# FLD_Logic_autorouted.net
KiCad netlist of a schematic drawn in EAGLE
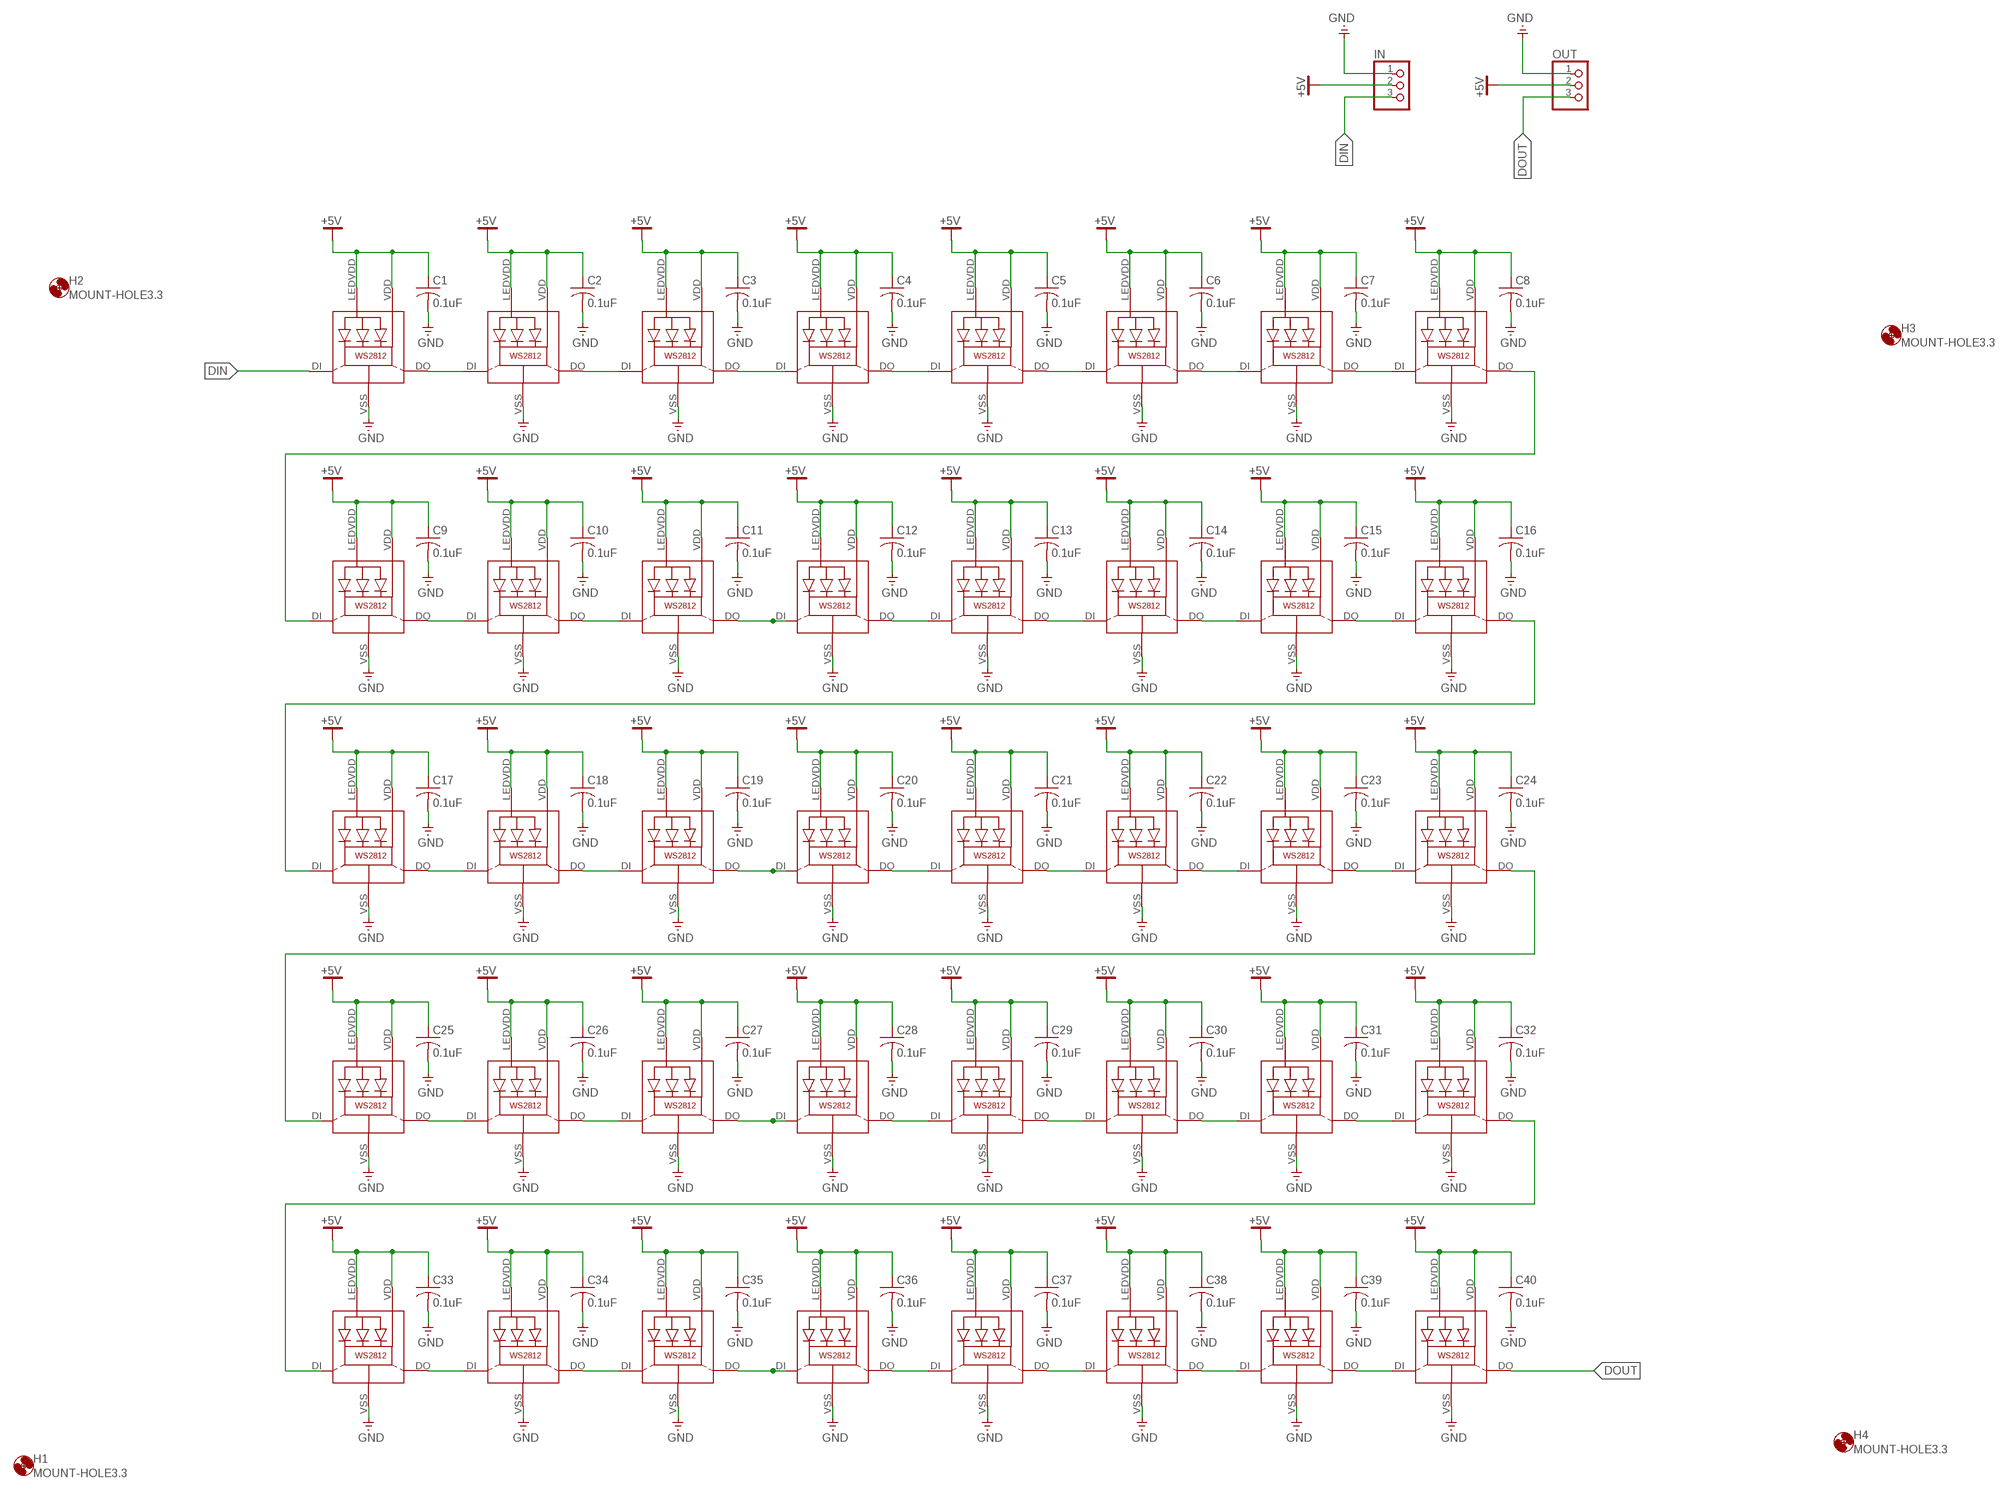
[diagram p0: schematic, sheet 1]

(export (version "E")
  (design (tool "Eeschema 10.0.6"))
  (components
    (comp (ref "C1")
      (value "0.1uF")
      (footprint "eagle-import:C0603")
      (libsource (lib "eagle-import") (part "C-USC0603"))
    )
    (comp (ref "C2")
      (value "0.1uF")
      (footprint "eagle-import:C0603")
      (libsource (lib "eagle-import") (part "C-USC0603"))
    )
    (comp (ref "C3")
      (value "0.1uF")
      (footprint "eagle-import:C0603")
      (libsource (lib "eagle-import") (part "C-USC0603"))
    )
    (comp (ref "C4")
      (value "0.1uF")
      (footprint "eagle-import:C0603")
      (libsource (lib "eagle-import") (part "C-USC0603"))
    )
    (comp (ref "C5")
      (value "0.1uF")
      (footprint "eagle-import:C0603")
      (libsource (lib "eagle-import") (part "C-USC0603"))
    )
    (comp (ref "C6")
      (value "0.1uF")
      (footprint "eagle-import:C0603")
      (libsource (lib "eagle-import") (part "C-USC0603"))
    )
    (comp (ref "C7")
      (value "0.1uF")
      (footprint "eagle-import:C0603")
      (libsource (lib "eagle-import") (part "C-USC0603"))
    )
    (comp (ref "C8")
      (value "0.1uF")
      (footprint "eagle-import:C0603")
      (libsource (lib "eagle-import") (part "C-USC0603"))
    )
    (comp (ref "C9")
      (value "0.1uF")
      (footprint "eagle-import:C0603")
      (libsource (lib "eagle-import") (part "C-USC0603"))
    )
    (comp (ref "C10")
      (value "0.1uF")
      (footprint "eagle-import:C0603")
      (libsource (lib "eagle-import") (part "C-USC0603"))
    )
    (comp (ref "C11")
      (value "0.1uF")
      (footprint "eagle-import:C0603")
      (libsource (lib "eagle-import") (part "C-USC0603"))
    )
    (comp (ref "C12")
      (value "0.1uF")
      (footprint "eagle-import:C0603")
      (libsource (lib "eagle-import") (part "C-USC0603"))
    )
    (comp (ref "C13")
      (value "0.1uF")
      (footprint "eagle-import:C0603")
      (libsource (lib "eagle-import") (part "C-USC0603"))
    )
    (comp (ref "C14")
      (value "0.1uF")
      (footprint "eagle-import:C0603")
      (libsource (lib "eagle-import") (part "C-USC0603"))
    )
    (comp (ref "C15")
      (value "0.1uF")
      (footprint "eagle-import:C0603")
      (libsource (lib "eagle-import") (part "C-USC0603"))
    )
    (comp (ref "C16")
      (value "0.1uF")
      (footprint "eagle-import:C0603")
      (libsource (lib "eagle-import") (part "C-USC0603"))
    )
    (comp (ref "C17")
      (value "0.1uF")
      (footprint "eagle-import:C0603")
      (libsource (lib "eagle-import") (part "C-USC0603"))
    )
    (comp (ref "C18")
      (value "0.1uF")
      (footprint "eagle-import:C0603")
      (libsource (lib "eagle-import") (part "C-USC0603"))
    )
    (comp (ref "C19")
      (value "0.1uF")
      (footprint "eagle-import:C0603")
      (libsource (lib "eagle-import") (part "C-USC0603"))
    )
    (comp (ref "C20")
      (value "0.1uF")
      (footprint "eagle-import:C0603")
      (libsource (lib "eagle-import") (part "C-USC0603"))
    )
    (comp (ref "C21")
      (value "0.1uF")
      (footprint "eagle-import:C0603")
      (libsource (lib "eagle-import") (part "C-USC0603"))
    )
    (comp (ref "C22")
      (value "0.1uF")
      (footprint "eagle-import:C0603")
      (libsource (lib "eagle-import") (part "C-USC0603"))
    )
    (comp (ref "C23")
      (value "0.1uF")
      (footprint "eagle-import:C0603")
      (libsource (lib "eagle-import") (part "C-USC0603"))
    )
    (comp (ref "C24")
      (value "0.1uF")
      (footprint "eagle-import:C0603")
      (libsource (lib "eagle-import") (part "C-USC0603"))
    )
    (comp (ref "C25")
      (value "0.1uF")
      (footprint "eagle-import:C0603")
      (libsource (lib "eagle-import") (part "C-USC0603"))
    )
    (comp (ref "C26")
      (value "0.1uF")
      (footprint "eagle-import:C0603")
      (libsource (lib "eagle-import") (part "C-USC0603"))
    )
    (comp (ref "C27")
      (value "0.1uF")
      (footprint "eagle-import:C0603")
      (libsource (lib "eagle-import") (part "C-USC0603"))
    )
    (comp (ref "C28")
      (value "0.1uF")
      (footprint "eagle-import:C0603")
      (libsource (lib "eagle-import") (part "C-USC0603"))
    )
    (comp (ref "C29")
      (value "0.1uF")
      (footprint "eagle-import:C0603")
      (libsource (lib "eagle-import") (part "C-USC0603"))
    )
    (comp (ref "C30")
      (value "0.1uF")
      (footprint "eagle-import:C0603")
      (libsource (lib "eagle-import") (part "C-USC0603"))
    )
    (comp (ref "C31")
      (value "0.1uF")
      (footprint "eagle-import:C0603")
      (libsource (lib "eagle-import") (part "C-USC0603"))
    )
    (comp (ref "C32")
      (value "0.1uF")
      (footprint "eagle-import:C0603")
      (libsource (lib "eagle-import") (part "C-USC0603"))
    )
    (comp (ref "C33")
      (value "0.1uF")
      (footprint "eagle-import:C0603")
      (libsource (lib "eagle-import") (part "C-USC0603"))
    )
    (comp (ref "C34")
      (value "0.1uF")
      (footprint "eagle-import:C0603")
      (libsource (lib "eagle-import") (part "C-USC0603"))
    )
    (comp (ref "C35")
      (value "0.1uF")
      (footprint "eagle-import:C0603")
      (libsource (lib "eagle-import") (part "C-USC0603"))
    )
    (comp (ref "C36")
      (value "0.1uF")
      (footprint "eagle-import:C0603")
      (libsource (lib "eagle-import") (part "C-USC0603"))
    )
    (comp (ref "C37")
      (value "0.1uF")
      (footprint "eagle-import:C0603")
      (libsource (lib "eagle-import") (part "C-USC0603"))
    )
    (comp (ref "C38")
      (value "0.1uF")
      (footprint "eagle-import:C0603")
      (libsource (lib "eagle-import") (part "C-USC0603"))
    )
    (comp (ref "C39")
      (value "0.1uF")
      (footprint "eagle-import:C0603")
      (libsource (lib "eagle-import") (part "C-USC0603"))
    )
    (comp (ref "C40")
      (value "0.1uF")
      (footprint "eagle-import:C0603")
      (libsource (lib "eagle-import") (part "C-USC0603"))
    )
    (comp (ref "H1")
      (value "MOUNT-HOLE3.3")
      (footprint "eagle-import:3,3")
      (libsource (lib "eagle-import") (part "MOUNT-HOLE3.3"))
    )
    (comp (ref "H2")
      (value "MOUNT-HOLE3.3")
      (footprint "eagle-import:3,3")
      (libsource (lib "eagle-import") (part "MOUNT-HOLE3.3"))
    )
    (comp (ref "H3")
      (value "MOUNT-HOLE3.3")
      (footprint "eagle-import:3,3")
      (libsource (lib "eagle-import") (part "MOUNT-HOLE3.3"))
    )
    (comp (ref "H4")
      (value "MOUNT-HOLE3.3")
      (footprint "eagle-import:3,3")
      (libsource (lib "eagle-import") (part "MOUNT-HOLE3.3"))
    )
    (comp (ref "IN")
      (value "PINHD-1X3")
      (footprint "eagle-import:1X03")
      (libsource (lib "eagle-import") (part "PINHD-1X3"))
    )
    (comp (ref "LED1")
      (value "WS2812")
      (footprint "eagle-import:WS2812")
      (libsource (lib "eagle-import") (part "WS2812"))
    )
    (comp (ref "LED2")
      (value "WS2812")
      (footprint "eagle-import:WS2812")
      (libsource (lib "eagle-import") (part "WS2812"))
    )
    (comp (ref "LED3")
      (value "WS2812")
      (footprint "eagle-import:WS2812")
      (libsource (lib "eagle-import") (part "WS2812"))
    )
    (comp (ref "LED4")
      (value "WS2812")
      (footprint "eagle-import:WS2812")
      (libsource (lib "eagle-import") (part "WS2812"))
    )
    (comp (ref "LED5")
      (value "WS2812")
      (footprint "eagle-import:WS2812")
      (libsource (lib "eagle-import") (part "WS2812"))
    )
    (comp (ref "LED6")
      (value "WS2812")
      (footprint "eagle-import:WS2812")
      (libsource (lib "eagle-import") (part "WS2812"))
    )
    (comp (ref "LED7")
      (value "WS2812")
      (footprint "eagle-import:WS2812")
      (libsource (lib "eagle-import") (part "WS2812"))
    )
    (comp (ref "LED8")
      (value "WS2812")
      (footprint "eagle-import:WS2812")
      (libsource (lib "eagle-import") (part "WS2812"))
    )
    (comp (ref "LED9")
      (value "WS2812")
      (footprint "eagle-import:WS2812")
      (libsource (lib "eagle-import") (part "WS2812"))
    )
    (comp (ref "LED10")
      (value "WS2812")
      (footprint "eagle-import:WS2812")
      (libsource (lib "eagle-import") (part "WS2812"))
    )
    (comp (ref "LED11")
      (value "WS2812")
      (footprint "eagle-import:WS2812")
      (libsource (lib "eagle-import") (part "WS2812"))
    )
    (comp (ref "LED12")
      (value "WS2812")
      (footprint "eagle-import:WS2812")
      (libsource (lib "eagle-import") (part "WS2812"))
    )
    (comp (ref "LED13")
      (value "WS2812")
      (footprint "eagle-import:WS2812")
      (libsource (lib "eagle-import") (part "WS2812"))
    )
    (comp (ref "LED14")
      (value "WS2812")
      (footprint "eagle-import:WS2812")
      (libsource (lib "eagle-import") (part "WS2812"))
    )
    (comp (ref "LED15")
      (value "WS2812")
      (footprint "eagle-import:WS2812")
      (libsource (lib "eagle-import") (part "WS2812"))
    )
    (comp (ref "LED16")
      (value "WS2812")
      (footprint "eagle-import:WS2812")
      (libsource (lib "eagle-import") (part "WS2812"))
    )
    (comp (ref "LED17")
      (value "WS2812")
      (footprint "eagle-import:WS2812")
      (libsource (lib "eagle-import") (part "WS2812"))
    )
    (comp (ref "LED18")
      (value "WS2812")
      (footprint "eagle-import:WS2812")
      (libsource (lib "eagle-import") (part "WS2812"))
    )
    (comp (ref "LED19")
      (value "WS2812")
      (footprint "eagle-import:WS2812")
      (libsource (lib "eagle-import") (part "WS2812"))
    )
    (comp (ref "LED20")
      (value "WS2812")
      (footprint "eagle-import:WS2812")
      (libsource (lib "eagle-import") (part "WS2812"))
    )
    (comp (ref "LED21")
      (value "WS2812")
      (footprint "eagle-import:WS2812")
      (libsource (lib "eagle-import") (part "WS2812"))
    )
    (comp (ref "LED22")
      (value "WS2812")
      (footprint "eagle-import:WS2812")
      (libsource (lib "eagle-import") (part "WS2812"))
    )
    (comp (ref "LED23")
      (value "WS2812")
      (footprint "eagle-import:WS2812")
      (libsource (lib "eagle-import") (part "WS2812"))
    )
    (comp (ref "LED24")
      (value "WS2812")
      (footprint "eagle-import:WS2812")
      (libsource (lib "eagle-import") (part "WS2812"))
    )
    (comp (ref "LED25")
      (value "WS2812")
      (footprint "eagle-import:WS2812")
      (libsource (lib "eagle-import") (part "WS2812"))
    )
    (comp (ref "LED26")
      (value "WS2812")
      (footprint "eagle-import:WS2812")
      (libsource (lib "eagle-import") (part "WS2812"))
    )
    (comp (ref "LED27")
      (value "WS2812")
      (footprint "eagle-import:WS2812")
      (libsource (lib "eagle-import") (part "WS2812"))
    )
    (comp (ref "LED28")
      (value "WS2812")
      (footprint "eagle-import:WS2812")
      (libsource (lib "eagle-import") (part "WS2812"))
    )
    (comp (ref "LED29")
      (value "WS2812")
      (footprint "eagle-import:WS2812")
      (libsource (lib "eagle-import") (part "WS2812"))
    )
    (comp (ref "LED30")
      (value "WS2812")
      (footprint "eagle-import:WS2812")
      (libsource (lib "eagle-import") (part "WS2812"))
    )
    (comp (ref "LED31")
      (value "WS2812")
      (footprint "eagle-import:WS2812")
      (libsource (lib "eagle-import") (part "WS2812"))
    )
    (comp (ref "LED32")
      (value "WS2812")
      (footprint "eagle-import:WS2812")
      (libsource (lib "eagle-import") (part "WS2812"))
    )
    (comp (ref "LED33")
      (value "WS2812")
      (footprint "eagle-import:WS2812")
      (libsource (lib "eagle-import") (part "WS2812"))
    )
    (comp (ref "LED34")
      (value "WS2812")
      (footprint "eagle-import:WS2812")
      (libsource (lib "eagle-import") (part "WS2812"))
    )
    (comp (ref "LED35")
      (value "WS2812")
      (footprint "eagle-import:WS2812")
      (libsource (lib "eagle-import") (part "WS2812"))
    )
    (comp (ref "LED36")
      (value "WS2812")
      (footprint "eagle-import:WS2812")
      (libsource (lib "eagle-import") (part "WS2812"))
    )
    (comp (ref "LED37")
      (value "WS2812")
      (footprint "eagle-import:WS2812")
      (libsource (lib "eagle-import") (part "WS2812"))
    )
    (comp (ref "LED38")
      (value "WS2812")
      (footprint "eagle-import:WS2812")
      (libsource (lib "eagle-import") (part "WS2812"))
    )
    (comp (ref "LED39")
      (value "WS2812")
      (footprint "eagle-import:WS2812")
      (libsource (lib "eagle-import") (part "WS2812"))
    )
    (comp (ref "LED40")
      (value "WS2812")
      (footprint "eagle-import:WS2812")
      (libsource (lib "eagle-import") (part "WS2812"))
    )
    (comp (ref "OUT")
      (value "PINHD-1X3")
      (footprint "eagle-import:1X03")
      (libsource (lib "eagle-import") (part "PINHD-1X3"))
    )
  )
  (nets
    (net (code "1") (name "+5V") (class "Default")
      (node (ref "C1") (pin "1") (pinfunction "1_1") (pintype "passive"))
      (node (ref "C10") (pin "1") (pinfunction "1_1") (pintype "passive"))
      (node (ref "C11") (pin "1") (pinfunction "1_1") (pintype "passive"))
      (node (ref "C12") (pin "1") (pinfunction "1_1") (pintype "passive"))
      (node (ref "C13") (pin "1") (pinfunction "1_1") (pintype "passive"))
      (node (ref "C14") (pin "1") (pinfunction "1_1") (pintype "passive"))
      (node (ref "C15") (pin "1") (pinfunction "1_1") (pintype "passive"))
      (node (ref "C16") (pin "1") (pinfunction "1_1") (pintype "passive"))
      (node (ref "C17") (pin "1") (pinfunction "1_1") (pintype "passive"))
      (node (ref "C18") (pin "1") (pinfunction "1_1") (pintype "passive"))
      (node (ref "C19") (pin "1") (pinfunction "1_1") (pintype "passive"))
      (node (ref "C2") (pin "1") (pinfunction "1_1") (pintype "passive"))
      (node (ref "C20") (pin "1") (pinfunction "1_1") (pintype "passive"))
      (node (ref "C21") (pin "1") (pinfunction "1_1") (pintype "passive"))
      (node (ref "C22") (pin "1") (pinfunction "1_1") (pintype "passive"))
      (node (ref "C23") (pin "1") (pinfunction "1_1") (pintype "passive"))
      (node (ref "C24") (pin "1") (pinfunction "1_1") (pintype "passive"))
      (node (ref "C25") (pin "1") (pinfunction "1_1") (pintype "passive"))
      (node (ref "C26") (pin "1") (pinfunction "1_1") (pintype "passive"))
      (node (ref "C27") (pin "1") (pinfunction "1_1") (pintype "passive"))
      (node (ref "C28") (pin "1") (pinfunction "1_1") (pintype "passive"))
      (node (ref "C29") (pin "1") (pinfunction "1_1") (pintype "passive"))
      (node (ref "C3") (pin "1") (pinfunction "1_1") (pintype "passive"))
      (node (ref "C30") (pin "1") (pinfunction "1_1") (pintype "passive"))
      (node (ref "C31") (pin "1") (pinfunction "1_1") (pintype "passive"))
      (node (ref "C32") (pin "1") (pinfunction "1_1") (pintype "passive"))
      (node (ref "C33") (pin "1") (pinfunction "1_1") (pintype "passive"))
      (node (ref "C34") (pin "1") (pinfunction "1_1") (pintype "passive"))
      (node (ref "C35") (pin "1") (pinfunction "1_1") (pintype "passive"))
      (node (ref "C36") (pin "1") (pinfunction "1_1") (pintype "passive"))
      (node (ref "C37") (pin "1") (pinfunction "1_1") (pintype "passive"))
      (node (ref "C38") (pin "1") (pinfunction "1_1") (pintype "passive"))
      (node (ref "C39") (pin "1") (pinfunction "1_1") (pintype "passive"))
      (node (ref "C4") (pin "1") (pinfunction "1_1") (pintype "passive"))
      (node (ref "C40") (pin "1") (pinfunction "1_1") (pintype "passive"))
      (node (ref "C5") (pin "1") (pinfunction "1_1") (pintype "passive"))
      (node (ref "C6") (pin "1") (pinfunction "1_1") (pintype "passive"))
      (node (ref "C7") (pin "1") (pinfunction "1_1") (pintype "passive"))
      (node (ref "C8") (pin "1") (pinfunction "1_1") (pintype "passive"))
      (node (ref "C9") (pin "1") (pinfunction "1_1") (pintype "passive"))
      (node (ref "IN") (pin "2") (pinfunction "2_2") (pintype "passive"))
      (node (ref "LED1") (pin "LEDVDD") (pinfunction "LEDVDD_LEDVDD") (pintype "power_in"))
      (node (ref "LED1") (pin "VDD") (pinfunction "VDD_VDD") (pintype "power_in"))
      (node (ref "LED10") (pin "LEDVDD") (pinfunction "LEDVDD_LEDVDD") (pintype "power_in"))
      (node (ref "LED10") (pin "VDD") (pinfunction "VDD_VDD") (pintype "power_in"))
      (node (ref "LED11") (pin "LEDVDD") (pinfunction "LEDVDD_LEDVDD") (pintype "power_in"))
      (node (ref "LED11") (pin "VDD") (pinfunction "VDD_VDD") (pintype "power_in"))
      (node (ref "LED12") (pin "LEDVDD") (pinfunction "LEDVDD_LEDVDD") (pintype "power_in"))
      (node (ref "LED12") (pin "VDD") (pinfunction "VDD_VDD") (pintype "power_in"))
      (node (ref "LED13") (pin "LEDVDD") (pinfunction "LEDVDD_LEDVDD") (pintype "power_in"))
      (node (ref "LED13") (pin "VDD") (pinfunction "VDD_VDD") (pintype "power_in"))
      (node (ref "LED14") (pin "LEDVDD") (pinfunction "LEDVDD_LEDVDD") (pintype "power_in"))
      (node (ref "LED14") (pin "VDD") (pinfunction "VDD_VDD") (pintype "power_in"))
      (node (ref "LED15") (pin "LEDVDD") (pinfunction "LEDVDD_LEDVDD") (pintype "power_in"))
      (node (ref "LED15") (pin "VDD") (pinfunction "VDD_VDD") (pintype "power_in"))
      (node (ref "LED16") (pin "LEDVDD") (pinfunction "LEDVDD_LEDVDD") (pintype "power_in"))
      (node (ref "LED16") (pin "VDD") (pinfunction "VDD_VDD") (pintype "power_in"))
      (node (ref "LED17") (pin "LEDVDD") (pinfunction "LEDVDD_LEDVDD") (pintype "power_in"))
      (node (ref "LED17") (pin "VDD") (pinfunction "VDD_VDD") (pintype "power_in"))
      (node (ref "LED18") (pin "LEDVDD") (pinfunction "LEDVDD_LEDVDD") (pintype "power_in"))
      (node (ref "LED18") (pin "VDD") (pinfunction "VDD_VDD") (pintype "power_in"))
      (node (ref "LED19") (pin "LEDVDD") (pinfunction "LEDVDD_LEDVDD") (pintype "power_in"))
      (node (ref "LED19") (pin "VDD") (pinfunction "VDD_VDD") (pintype "power_in"))
      (node (ref "LED2") (pin "LEDVDD") (pinfunction "LEDVDD_LEDVDD") (pintype "power_in"))
      (node (ref "LED2") (pin "VDD") (pinfunction "VDD_VDD") (pintype "power_in"))
      (node (ref "LED20") (pin "LEDVDD") (pinfunction "LEDVDD_LEDVDD") (pintype "power_in"))
      (node (ref "LED20") (pin "VDD") (pinfunction "VDD_VDD") (pintype "power_in"))
      (node (ref "LED21") (pin "LEDVDD") (pinfunction "LEDVDD_LEDVDD") (pintype "power_in"))
      (node (ref "LED21") (pin "VDD") (pinfunction "VDD_VDD") (pintype "power_in"))
      (node (ref "LED22") (pin "LEDVDD") (pinfunction "LEDVDD_LEDVDD") (pintype "power_in"))
      (node (ref "LED22") (pin "VDD") (pinfunction "VDD_VDD") (pintype "power_in"))
      (node (ref "LED23") (pin "LEDVDD") (pinfunction "LEDVDD_LEDVDD") (pintype "power_in"))
      (node (ref "LED23") (pin "VDD") (pinfunction "VDD_VDD") (pintype "power_in"))
      (node (ref "LED24") (pin "LEDVDD") (pinfunction "LEDVDD_LEDVDD") (pintype "power_in"))
      (node (ref "LED24") (pin "VDD") (pinfunction "VDD_VDD") (pintype "power_in"))
      (node (ref "LED25") (pin "LEDVDD") (pinfunction "LEDVDD_LEDVDD") (pintype "power_in"))
      (node (ref "LED25") (pin "VDD") (pinfunction "VDD_VDD") (pintype "power_in"))
      (node (ref "LED26") (pin "LEDVDD") (pinfunction "LEDVDD_LEDVDD") (pintype "power_in"))
      (node (ref "LED26") (pin "VDD") (pinfunction "VDD_VDD") (pintype "power_in"))
      (node (ref "LED27") (pin "LEDVDD") (pinfunction "LEDVDD_LEDVDD") (pintype "power_in"))
      (node (ref "LED27") (pin "VDD") (pinfunction "VDD_VDD") (pintype "power_in"))
      (node (ref "LED28") (pin "LEDVDD") (pinfunction "LEDVDD_LEDVDD") (pintype "power_in"))
      (node (ref "LED28") (pin "VDD") (pinfunction "VDD_VDD") (pintype "power_in"))
      (node (ref "LED29") (pin "LEDVDD") (pinfunction "LEDVDD_LEDVDD") (pintype "power_in"))
      (node (ref "LED29") (pin "VDD") (pinfunction "VDD_VDD") (pintype "power_in"))
      (node (ref "LED3") (pin "LEDVDD") (pinfunction "LEDVDD_LEDVDD") (pintype "power_in"))
      (node (ref "LED3") (pin "VDD") (pinfunction "VDD_VDD") (pintype "power_in"))
      (node (ref "LED30") (pin "LEDVDD") (pinfunction "LEDVDD_LEDVDD") (pintype "power_in"))
      (node (ref "LED30") (pin "VDD") (pinfunction "VDD_VDD") (pintype "power_in"))
      (node (ref "LED31") (pin "LEDVDD") (pinfunction "LEDVDD_LEDVDD") (pintype "power_in"))
      (node (ref "LED31") (pin "VDD") (pinfunction "VDD_VDD") (pintype "power_in"))
      (node (ref "LED32") (pin "LEDVDD") (pinfunction "LEDVDD_LEDVDD") (pintype "power_in"))
      (node (ref "LED32") (pin "VDD") (pinfunction "VDD_VDD") (pintype "power_in"))
      (node (ref "LED33") (pin "LEDVDD") (pinfunction "LEDVDD_LEDVDD") (pintype "power_in"))
      (node (ref "LED33") (pin "VDD") (pinfunction "VDD_VDD") (pintype "power_in"))
      (node (ref "LED34") (pin "LEDVDD") (pinfunction "LEDVDD_LEDVDD") (pintype "power_in"))
      (node (ref "LED34") (pin "VDD") (pinfunction "VDD_VDD") (pintype "power_in"))
      (node (ref "LED35") (pin "LEDVDD") (pinfunction "LEDVDD_LEDVDD") (pintype "power_in"))
      (node (ref "LED35") (pin "VDD") (pinfunction "VDD_VDD") (pintype "power_in"))
      (node (ref "LED36") (pin "LEDVDD") (pinfunction "LEDVDD_LEDVDD") (pintype "power_in"))
      (node (ref "LED36") (pin "VDD") (pinfunction "VDD_VDD") (pintype "power_in"))
      (node (ref "LED37") (pin "LEDVDD") (pinfunction "LEDVDD_LEDVDD") (pintype "power_in"))
      (node (ref "LED37") (pin "VDD") (pinfunction "VDD_VDD") (pintype "power_in"))
      (node (ref "LED38") (pin "LEDVDD") (pinfunction "LEDVDD_LEDVDD") (pintype "power_in"))
      (node (ref "LED38") (pin "VDD") (pinfunction "VDD_VDD") (pintype "power_in"))
      (node (ref "LED39") (pin "LEDVDD") (pinfunction "LEDVDD_LEDVDD") (pintype "power_in"))
      (node (ref "LED39") (pin "VDD") (pinfunction "VDD_VDD") (pintype "power_in"))
      (node (ref "LED4") (pin "LEDVDD") (pinfunction "LEDVDD_LEDVDD") (pintype "power_in"))
      (node (ref "LED4") (pin "VDD") (pinfunction "VDD_VDD") (pintype "power_in"))
      (node (ref "LED40") (pin "LEDVDD") (pinfunction "LEDVDD_LEDVDD") (pintype "power_in"))
      (node (ref "LED40") (pin "VDD") (pinfunction "VDD_VDD") (pintype "power_in"))
      (node (ref "LED5") (pin "LEDVDD") (pinfunction "LEDVDD_LEDVDD") (pintype "power_in"))
      (node (ref "LED5") (pin "VDD") (pinfunction "VDD_VDD") (pintype "power_in"))
      (node (ref "LED6") (pin "LEDVDD") (pinfunction "LEDVDD_LEDVDD") (pintype "power_in"))
      (node (ref "LED6") (pin "VDD") (pinfunction "VDD_VDD") (pintype "power_in"))
      (node (ref "LED7") (pin "LEDVDD") (pinfunction "LEDVDD_LEDVDD") (pintype "power_in"))
      (node (ref "LED7") (pin "VDD") (pinfunction "VDD_VDD") (pintype "power_in"))
      (node (ref "LED8") (pin "LEDVDD") (pinfunction "LEDVDD_LEDVDD") (pintype "power_in"))
      (node (ref "LED8") (pin "VDD") (pinfunction "VDD_VDD") (pintype "power_in"))
      (node (ref "LED9") (pin "LEDVDD") (pinfunction "LEDVDD_LEDVDD") (pintype "power_in"))
      (node (ref "LED9") (pin "VDD") (pinfunction "VDD_VDD") (pintype "power_in"))
      (node (ref "OUT") (pin "2") (pinfunction "2_2") (pintype "passive"))
    )
    (net (code "2") (name "DIN") (class "Default")
      (node (ref "IN") (pin "3") (pinfunction "3_3") (pintype "passive"))
      (node (ref "LED1") (pin "DI") (pinfunction "DI_DI") (pintype "input"))
    )
    (net (code "3") (name "DOUT") (class "Default")
      (node (ref "LED40") (pin "DO") (pinfunction "DO_DO") (pintype "output"))
      (node (ref "OUT") (pin "3") (pinfunction "3_3") (pintype "passive"))
    )
    (net (code "4") (name "GND") (class "Default")
      (node (ref "C1") (pin "2") (pinfunction "2_2") (pintype "passive"))
      (node (ref "C10") (pin "2") (pinfunction "2_2") (pintype "passive"))
      (node (ref "C11") (pin "2") (pinfunction "2_2") (pintype "passive"))
      (node (ref "C12") (pin "2") (pinfunction "2_2") (pintype "passive"))
      (node (ref "C13") (pin "2") (pinfunction "2_2") (pintype "passive"))
      (node (ref "C14") (pin "2") (pinfunction "2_2") (pintype "passive"))
      (node (ref "C15") (pin "2") (pinfunction "2_2") (pintype "passive"))
      (node (ref "C16") (pin "2") (pinfunction "2_2") (pintype "passive"))
      (node (ref "C17") (pin "2") (pinfunction "2_2") (pintype "passive"))
      (node (ref "C18") (pin "2") (pinfunction "2_2") (pintype "passive"))
      (node (ref "C19") (pin "2") (pinfunction "2_2") (pintype "passive"))
      (node (ref "C2") (pin "2") (pinfunction "2_2") (pintype "passive"))
      (node (ref "C20") (pin "2") (pinfunction "2_2") (pintype "passive"))
      (node (ref "C21") (pin "2") (pinfunction "2_2") (pintype "passive"))
      (node (ref "C22") (pin "2") (pinfunction "2_2") (pintype "passive"))
      (node (ref "C23") (pin "2") (pinfunction "2_2") (pintype "passive"))
      (node (ref "C24") (pin "2") (pinfunction "2_2") (pintype "passive"))
      (node (ref "C25") (pin "2") (pinfunction "2_2") (pintype "passive"))
      (node (ref "C26") (pin "2") (pinfunction "2_2") (pintype "passive"))
      (node (ref "C27") (pin "2") (pinfunction "2_2") (pintype "passive"))
      (node (ref "C28") (pin "2") (pinfunction "2_2") (pintype "passive"))
      (node (ref "C29") (pin "2") (pinfunction "2_2") (pintype "passive"))
      (node (ref "C3") (pin "2") (pinfunction "2_2") (pintype "passive"))
      (node (ref "C30") (pin "2") (pinfunction "2_2") (pintype "passive"))
      (node (ref "C31") (pin "2") (pinfunction "2_2") (pintype "passive"))
      (node (ref "C32") (pin "2") (pinfunction "2_2") (pintype "passive"))
      (node (ref "C33") (pin "2") (pinfunction "2_2") (pintype "passive"))
      (node (ref "C34") (pin "2") (pinfunction "2_2") (pintype "passive"))
      (node (ref "C35") (pin "2") (pinfunction "2_2") (pintype "passive"))
      (node (ref "C36") (pin "2") (pinfunction "2_2") (pintype "passive"))
      (node (ref "C37") (pin "2") (pinfunction "2_2") (pintype "passive"))
      (node (ref "C38") (pin "2") (pinfunction "2_2") (pintype "passive"))
      (node (ref "C39") (pin "2") (pinfunction "2_2") (pintype "passive"))
      (node (ref "C4") (pin "2") (pinfunction "2_2") (pintype "passive"))
      (node (ref "C40") (pin "2") (pinfunction "2_2") (pintype "passive"))
      (node (ref "C5") (pin "2") (pinfunction "2_2") (pintype "passive"))
      (node (ref "C6") (pin "2") (pinfunction "2_2") (pintype "passive"))
      (node (ref "C7") (pin "2") (pinfunction "2_2") (pintype "passive"))
      (node (ref "C8") (pin "2") (pinfunction "2_2") (pintype "passive"))
      (node (ref "C9") (pin "2") (pinfunction "2_2") (pintype "passive"))
      (node (ref "IN") (pin "1") (pinfunction "1_1") (pintype "passive"))
      (node (ref "LED1") (pin "VSS") (pinfunction "GND_VSS") (pintype "power_in"))
      (node (ref "LED10") (pin "VSS") (pinfunction "GND_VSS") (pintype "power_in"))
      (node (ref "LED11") (pin "VSS") (pinfunction "GND_VSS") (pintype "power_in"))
      (node (ref "LED12") (pin "VSS") (pinfunction "GND_VSS") (pintype "power_in"))
      (node (ref "LED13") (pin "VSS") (pinfunction "GND_VSS") (pintype "power_in"))
      (node (ref "LED14") (pin "VSS") (pinfunction "GND_VSS") (pintype "power_in"))
      (node (ref "LED15") (pin "VSS") (pinfunction "GND_VSS") (pintype "power_in"))
      (node (ref "LED16") (pin "VSS") (pinfunction "GND_VSS") (pintype "power_in"))
      (node (ref "LED17") (pin "VSS") (pinfunction "GND_VSS") (pintype "power_in"))
      (node (ref "LED18") (pin "VSS") (pinfunction "GND_VSS") (pintype "power_in"))
      (node (ref "LED19") (pin "VSS") (pinfunction "GND_VSS") (pintype "power_in"))
      (node (ref "LED2") (pin "VSS") (pinfunction "GND_VSS") (pintype "power_in"))
      (node (ref "LED20") (pin "VSS") (pinfunction "GND_VSS") (pintype "power_in"))
      (node (ref "LED21") (pin "VSS") (pinfunction "GND_VSS") (pintype "power_in"))
      (node (ref "LED22") (pin "VSS") (pinfunction "GND_VSS") (pintype "power_in"))
      (node (ref "LED23") (pin "VSS") (pinfunction "GND_VSS") (pintype "power_in"))
      (node (ref "LED24") (pin "VSS") (pinfunction "GND_VSS") (pintype "power_in"))
      (node (ref "LED25") (pin "VSS") (pinfunction "GND_VSS") (pintype "power_in"))
      (node (ref "LED26") (pin "VSS") (pinfunction "GND_VSS") (pintype "power_in"))
      (node (ref "LED27") (pin "VSS") (pinfunction "GND_VSS") (pintype "power_in"))
      (node (ref "LED28") (pin "VSS") (pinfunction "GND_VSS") (pintype "power_in"))
      (node (ref "LED29") (pin "VSS") (pinfunction "GND_VSS") (pintype "power_in"))
      (node (ref "LED3") (pin "VSS") (pinfunction "GND_VSS") (pintype "power_in"))
      (node (ref "LED30") (pin "VSS") (pinfunction "GND_VSS") (pintype "power_in"))
      (node (ref "LED31") (pin "VSS") (pinfunction "GND_VSS") (pintype "power_in"))
      (node (ref "LED32") (pin "VSS") (pinfunction "GND_VSS") (pintype "power_in"))
      (node (ref "LED33") (pin "VSS") (pinfunction "GND_VSS") (pintype "power_in"))
      (node (ref "LED34") (pin "VSS") (pinfunction "GND_VSS") (pintype "power_in"))
      (node (ref "LED35") (pin "VSS") (pinfunction "GND_VSS") (pintype "power_in"))
      (node (ref "LED36") (pin "VSS") (pinfunction "GND_VSS") (pintype "power_in"))
      (node (ref "LED37") (pin "VSS") (pinfunction "GND_VSS") (pintype "power_in"))
      (node (ref "LED38") (pin "VSS") (pinfunction "GND_VSS") (pintype "power_in"))
      (node (ref "LED39") (pin "VSS") (pinfunction "GND_VSS") (pintype "power_in"))
      (node (ref "LED4") (pin "VSS") (pinfunction "GND_VSS") (pintype "power_in"))
      (node (ref "LED40") (pin "VSS") (pinfunction "GND_VSS") (pintype "power_in"))
      (node (ref "LED5") (pin "VSS") (pinfunction "GND_VSS") (pintype "power_in"))
      (node (ref "LED6") (pin "VSS") (pinfunction "GND_VSS") (pintype "power_in"))
      (node (ref "LED7") (pin "VSS") (pinfunction "GND_VSS") (pintype "power_in"))
      (node (ref "LED8") (pin "VSS") (pinfunction "GND_VSS") (pintype "power_in"))
      (node (ref "LED9") (pin "VSS") (pinfunction "GND_VSS") (pintype "power_in"))
      (node (ref "OUT") (pin "1") (pinfunction "1_1") (pintype "passive"))
    )
    (net (code "5") (name "Net-(LED1-PadDO)") (class "Default")
      (node (ref "LED1") (pin "DO") (pinfunction "DO_DO") (pintype "output"))
      (node (ref "LED2") (pin "DI") (pinfunction "DI_DI") (pintype "input"))
    )
    (net (code "6") (name "Net-(LED2-PadDO)") (class "Default")
      (node (ref "LED2") (pin "DO") (pinfunction "DO_DO") (pintype "output"))
      (node (ref "LED3") (pin "DI") (pinfunction "DI_DI") (pintype "input"))
    )
    (net (code "7") (name "Net-(LED4-PadDO)") (class "Default")
      (node (ref "LED4") (pin "DO") (pinfunction "DO_DO") (pintype "output"))
      (node (ref "LED5") (pin "DI") (pinfunction "DI_DI") (pintype "input"))
    )
    (net (code "8") (name "Net-(LED5-PadDO)") (class "Default")
      (node (ref "LED5") (pin "DO") (pinfunction "DO_DO") (pintype "output"))
      (node (ref "LED6") (pin "DI") (pinfunction "DI_DI") (pintype "input"))
    )
    (net (code "9") (name "Net-(LED6-PadDO)") (class "Default")
      (node (ref "LED6") (pin "DO") (pinfunction "DO_DO") (pintype "output"))
      (node (ref "LED7") (pin "DI") (pinfunction "DI_DI") (pintype "input"))
    )
    (net (code "10") (name "Net-(LED7-PadDO)") (class "Default")
      (node (ref "LED7") (pin "DO") (pinfunction "DO_DO") (pintype "output"))
      (node (ref "LED8") (pin "DI") (pinfunction "DI_DI") (pintype "input"))
    )
    (net (code "11") (name "Net-(LED8-PadDO)") (class "Default")
      (node (ref "LED8") (pin "DO") (pinfunction "DO_DO") (pintype "output"))
      (node (ref "LED9") (pin "DI") (pinfunction "DI_DI") (pintype "input"))
    )
    (net (code "12") (name "Net-(LED10-PadDI)") (class "Default")
      (node (ref "LED10") (pin "DI") (pinfunction "DI_DI") (pintype "input"))
      (node (ref "LED9") (pin "DO") (pinfunction "DO_DO") (pintype "output"))
    )
    (net (code "13") (name "Net-(LED10-PadDO)") (class "Default")
      (node (ref "LED10") (pin "DO") (pinfunction "DO_DO") (pintype "output"))
      (node (ref "LED11") (pin "DI") (pinfunction "DI_DI") (pintype "input"))
    )
    (net (code "14") (name "Net-(LED11-PadDO)") (class "Default")
      (node (ref "LED11") (pin "DO") (pinfunction "DO_DO") (pintype "output"))
      (node (ref "LED12") (pin "DI") (pinfunction "DI_DI") (pintype "input"))
    )
    (net (code "15") (name "Net-(LED12-PadDO)") (class "Default")
      (node (ref "LED12") (pin "DO") (pinfunction "DO_DO") (pintype "output"))
      (node (ref "LED13") (pin "DI") (pinfunction "DI_DI") (pintype "input"))
    )
    (net (code "16") (name "Net-(LED13-PadDO)") (class "Default")
      (node (ref "LED13") (pin "DO") (pinfunction "DO_DO") (pintype "output"))
      (node (ref "LED14") (pin "DI") (pinfunction "DI_DI") (pintype "input"))
    )
    (net (code "17") (name "Net-(LED14-PadDO)") (class "Default")
      (node (ref "LED14") (pin "DO") (pinfunction "DO_DO") (pintype "output"))
      (node (ref "LED15") (pin "DI") (pinfunction "DI_DI") (pintype "input"))
    )
    (net (code "18") (name "Net-(LED15-PadDO)") (class "Default")
      (node (ref "LED15") (pin "DO") (pinfunction "DO_DO") (pintype "output"))
      (node (ref "LED16") (pin "DI") (pinfunction "DI_DI") (pintype "input"))
    )
    (net (code "19") (name "Net-(LED16-PadDO)") (class "Default")
      (node (ref "LED16") (pin "DO") (pinfunction "DO_DO") (pintype "output"))
      (node (ref "LED17") (pin "DI") (pinfunction "DI_DI") (pintype "input"))
    )
    (net (code "20") (name "Net-(LED17-PadDO)") (class "Default")
      (node (ref "LED17") (pin "DO") (pinfunction "DO_DO") (pintype "output"))
      (node (ref "LED18") (pin "DI") (pinfunction "DI_DI") (pintype "input"))
    )
    (net (code "21") (name "Net-(LED18-PadDO)") (class "Default")
      (node (ref "LED18") (pin "DO") (pinfunction "DO_DO") (pintype "output"))
      (node (ref "LED19") (pin "DI") (pinfunction "DI_DI") (pintype "input"))
    )
    (net (code "22") (name "Net-(LED19-PadDO)") (class "Default")
      (node (ref "LED19") (pin "DO") (pinfunction "DO_DO") (pintype "output"))
      (node (ref "LED20") (pin "DI") (pinfunction "DI_DI") (pintype "input"))
    )
    (net (code "23") (name "Net-(LED20-PadDO)") (class "Default")
      (node (ref "LED20") (pin "DO") (pinfunction "DO_DO") (pintype "output"))
      (node (ref "LED21") (pin "DI") (pinfunction "DI_DI") (pintype "input"))
    )
    (net (code "24") (name "Net-(LED21-PadDO)") (class "Default")
      (node (ref "LED21") (pin "DO") (pinfunction "DO_DO") (pintype "output"))
      (node (ref "LED22") (pin "DI") (pinfunction "DI_DI") (pintype "input"))
    )
    (net (code "25") (name "Net-(LED22-PadDO)") (class "Default")
      (node (ref "LED22") (pin "DO") (pinfunction "DO_DO") (pintype "output"))
      (node (ref "LED23") (pin "DI") (pinfunction "DI_DI") (pintype "input"))
    )
    (net (code "26") (name "Net-(LED23-PadDO)") (class "Default")
      (node (ref "LED23") (pin "DO") (pinfunction "DO_DO") (pintype "output"))
      (node (ref "LED24") (pin "DI") (pinfunction "DI_DI") (pintype "input"))
    )
    (net (code "27") (name "Net-(LED25-PadDO)") (class "Default")
      (node (ref "LED25") (pin "DO") (pinfunction "DO_DO") (pintype "output"))
      (node (ref "LED26") (pin "DI") (pinfunction "DI_DI") (pintype "input"))
    )
    (net (code "28") (name "Net-(LED26-PadDO)") (class "Default")
      (node (ref "LED26") (pin "DO") (pinfunction "DO_DO") (pintype "output"))
      (node (ref "LED27") (pin "DI") (pinfunction "DI_DI") (pintype "input"))
    )
    (net (code "29") (name "Net-(LED27-PadDO)") (class "Default")
      (node (ref "LED27") (pin "DO") (pinfunction "DO_DO") (pintype "output"))
      (node (ref "LED28") (pin "DI") (pinfunction "DI_DI") (pintype "input"))
    )
    (net (code "30") (name "Net-(LED28-PadDO)") (class "Default")
      (node (ref "LED28") (pin "DO") (pinfunction "DO_DO") (pintype "output"))
      (node (ref "LED29") (pin "DI") (pinfunction "DI_DI") (pintype "input"))
    )
    (net (code "31") (name "Net-(LED29-PadDO)") (class "Default")
      (node (ref "LED29") (pin "DO") (pinfunction "DO_DO") (pintype "output"))
      (node (ref "LED30") (pin "DI") (pinfunction "DI_DI") (pintype "input"))
    )
    (net (code "32") (name "Net-(LED30-PadDO)") (class "Default")
      (node (ref "LED30") (pin "DO") (pinfunction "DO_DO") (pintype "output"))
      (node (ref "LED31") (pin "DI") (pinfunction "DI_DI") (pintype "input"))
    )
    (net (code "33") (name "Net-(LED31-PadDO)") (class "Default")
      (node (ref "LED31") (pin "DO") (pinfunction "DO_DO") (pintype "output"))
      (node (ref "LED32") (pin "DI") (pinfunction "DI_DI") (pintype "input"))
    )
    (net (code "34") (name "Net-(LED33-PadDO)") (class "Default")
      (node (ref "LED33") (pin "DO") (pinfunction "DO_DO") (pintype "output"))
      (node (ref "LED34") (pin "DI") (pinfunction "DI_DI") (pintype "input"))
    )
    (net (code "35") (name "Net-(LED34-PadDO)") (class "Default")
      (node (ref "LED34") (pin "DO") (pinfunction "DO_DO") (pintype "output"))
      (node (ref "LED35") (pin "DI") (pinfunction "DI_DI") (pintype "input"))
    )
    (net (code "36") (name "Net-(LED35-PadDO)") (class "Default")
      (node (ref "LED35") (pin "DO") (pinfunction "DO_DO") (pintype "output"))
      (node (ref "LED36") (pin "DI") (pinfunction "DI_DI") (pintype "input"))
    )
    (net (code "37") (name "Net-(LED36-PadDO)") (class "Default")
      (node (ref "LED36") (pin "DO") (pinfunction "DO_DO") (pintype "output"))
      (node (ref "LED37") (pin "DI") (pinfunction "DI_DI") (pintype "input"))
    )
    (net (code "38") (name "Net-(LED37-PadDO)") (class "Default")
      (node (ref "LED37") (pin "DO") (pinfunction "DO_DO") (pintype "output"))
      (node (ref "LED38") (pin "DI") (pinfunction "DI_DI") (pintype "input"))
    )
    (net (code "39") (name "Net-(LED38-PadDO)") (class "Default")
      (node (ref "LED38") (pin "DO") (pinfunction "DO_DO") (pintype "output"))
      (node (ref "LED39") (pin "DI") (pinfunction "DI_DI") (pintype "input"))
    )
    (net (code "40") (name "Net-(LED39-PadDO)") (class "Default")
      (node (ref "LED39") (pin "DO") (pinfunction "DO_DO") (pintype "output"))
      (node (ref "LED40") (pin "DI") (pinfunction "DI_DI") (pintype "input"))
    )
    (net (code "41") (name "unconnected-(LED3-PadDO)") (class "Default")
      (node (ref "LED3") (pin "DO") (pinfunction "DO_DO") (pintype "output"))
    )
    (net (code "42") (name "unconnected-(LED4-PadDI)") (class "Default")
      (node (ref "LED4") (pin "DI") (pinfunction "DI_DI") (pintype "input"))
    )
    (net (code "43") (name "unconnected-(LED24-PadDO)") (class "Default")
      (node (ref "LED24") (pin "DO") (pinfunction "DO_DO") (pintype "output"))
    )
    (net (code "44") (name "unconnected-(LED25-PadDI)") (class "Default")
      (node (ref "LED25") (pin "DI") (pinfunction "DI_DI") (pintype "input"))
    )
    (net (code "45") (name "unconnected-(LED32-PadDO)") (class "Default")
      (node (ref "LED32") (pin "DO") (pinfunction "DO_DO") (pintype "output"))
    )
    (net (code "46") (name "unconnected-(LED33-PadDI)") (class "Default")
      (node (ref "LED33") (pin "DI") (pinfunction "DI_DI") (pintype "input"))
    )
  )
)
